# 1602_arduino_ble.net
KiCad netlist of a schematic drawn in EAGLE
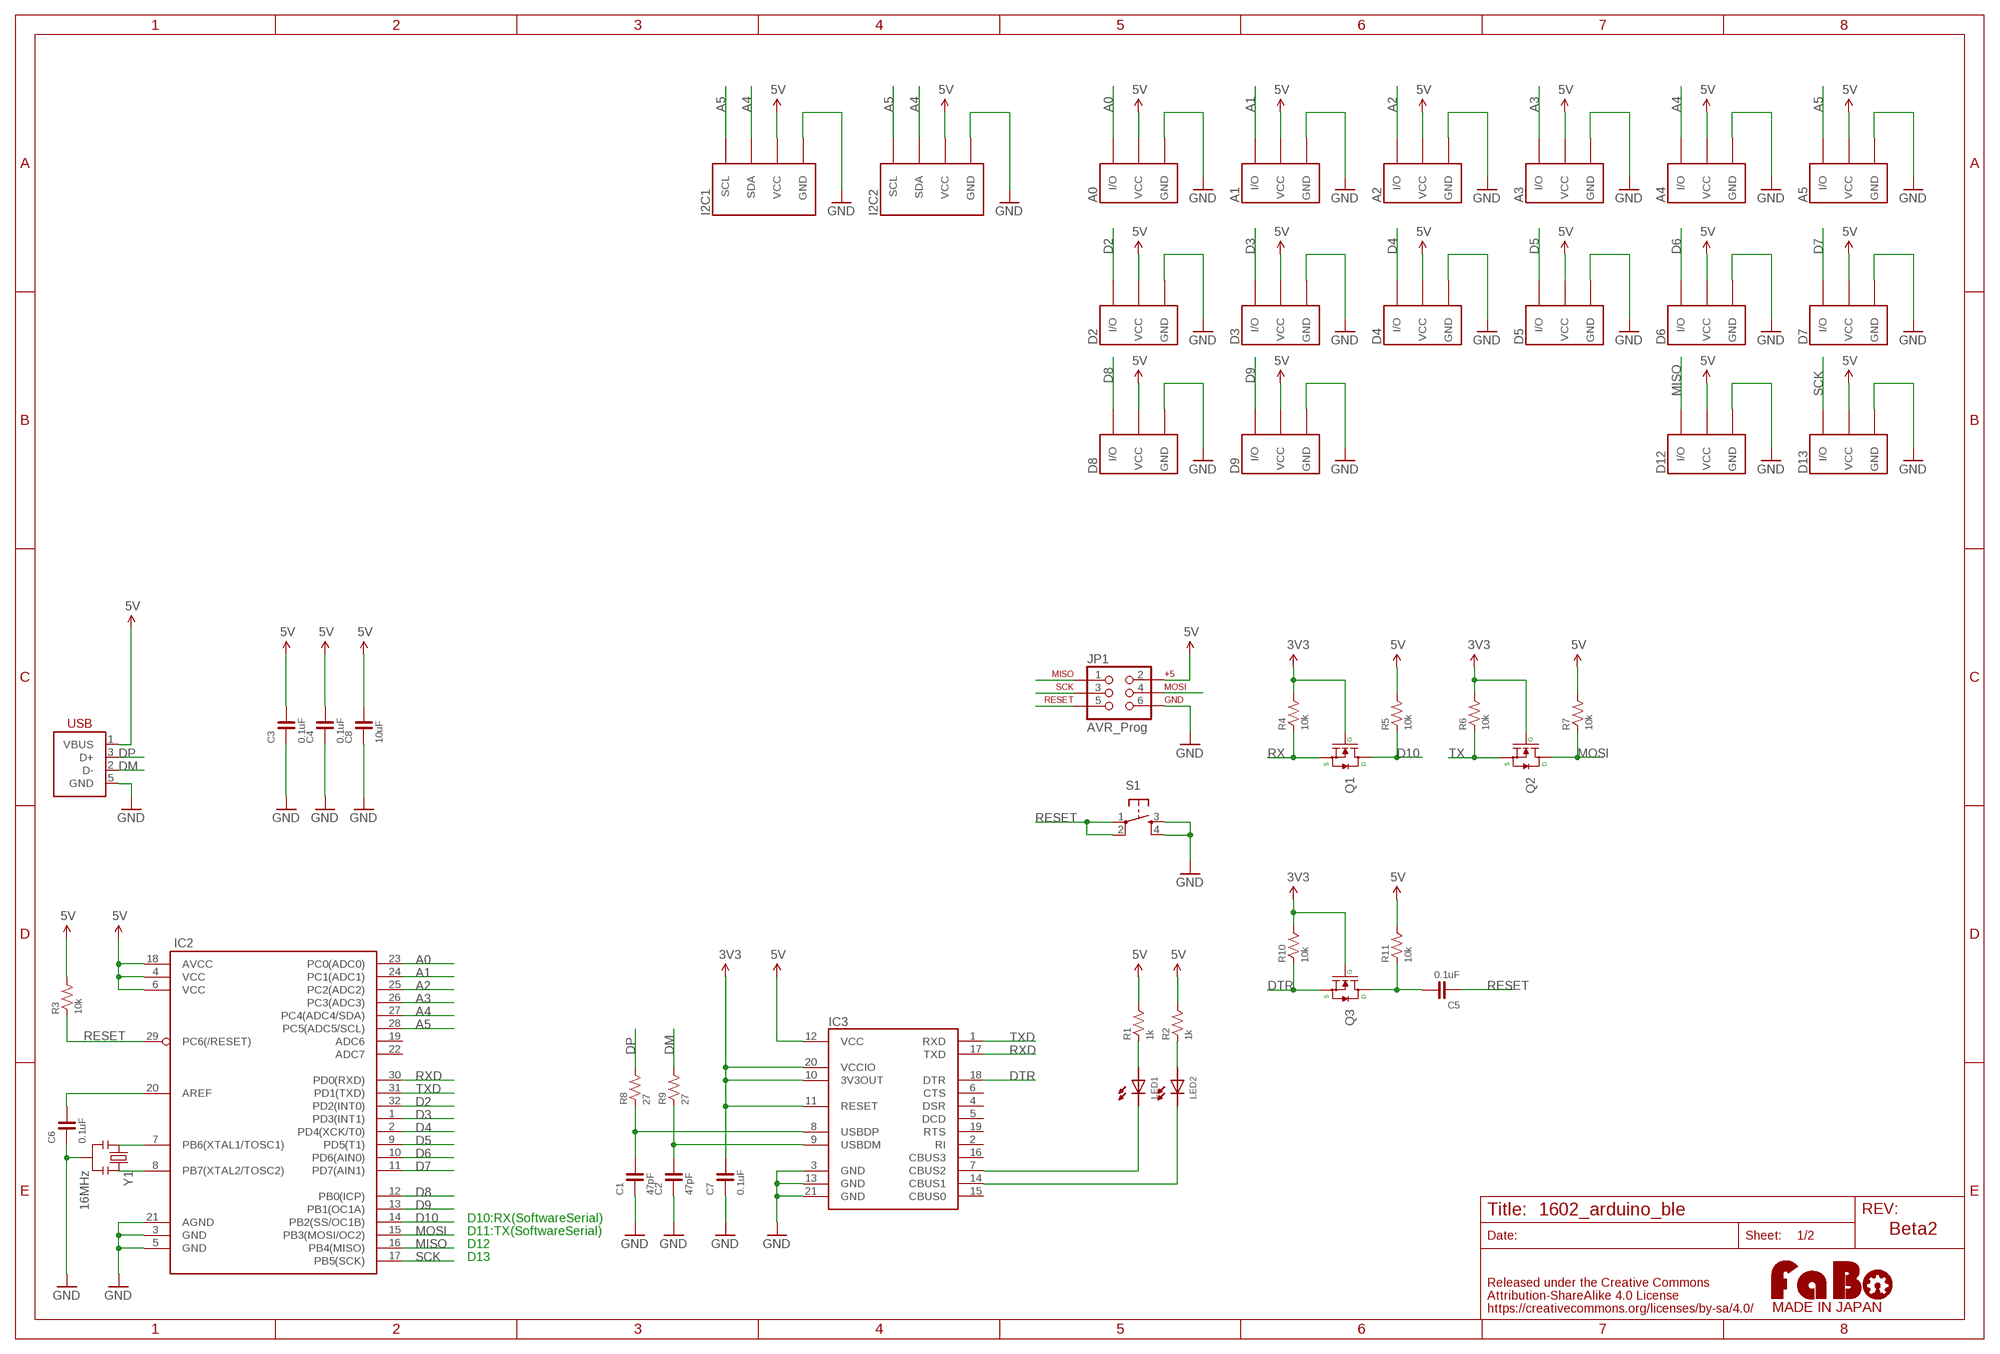
[diagram p0: schematic, sheet 1]
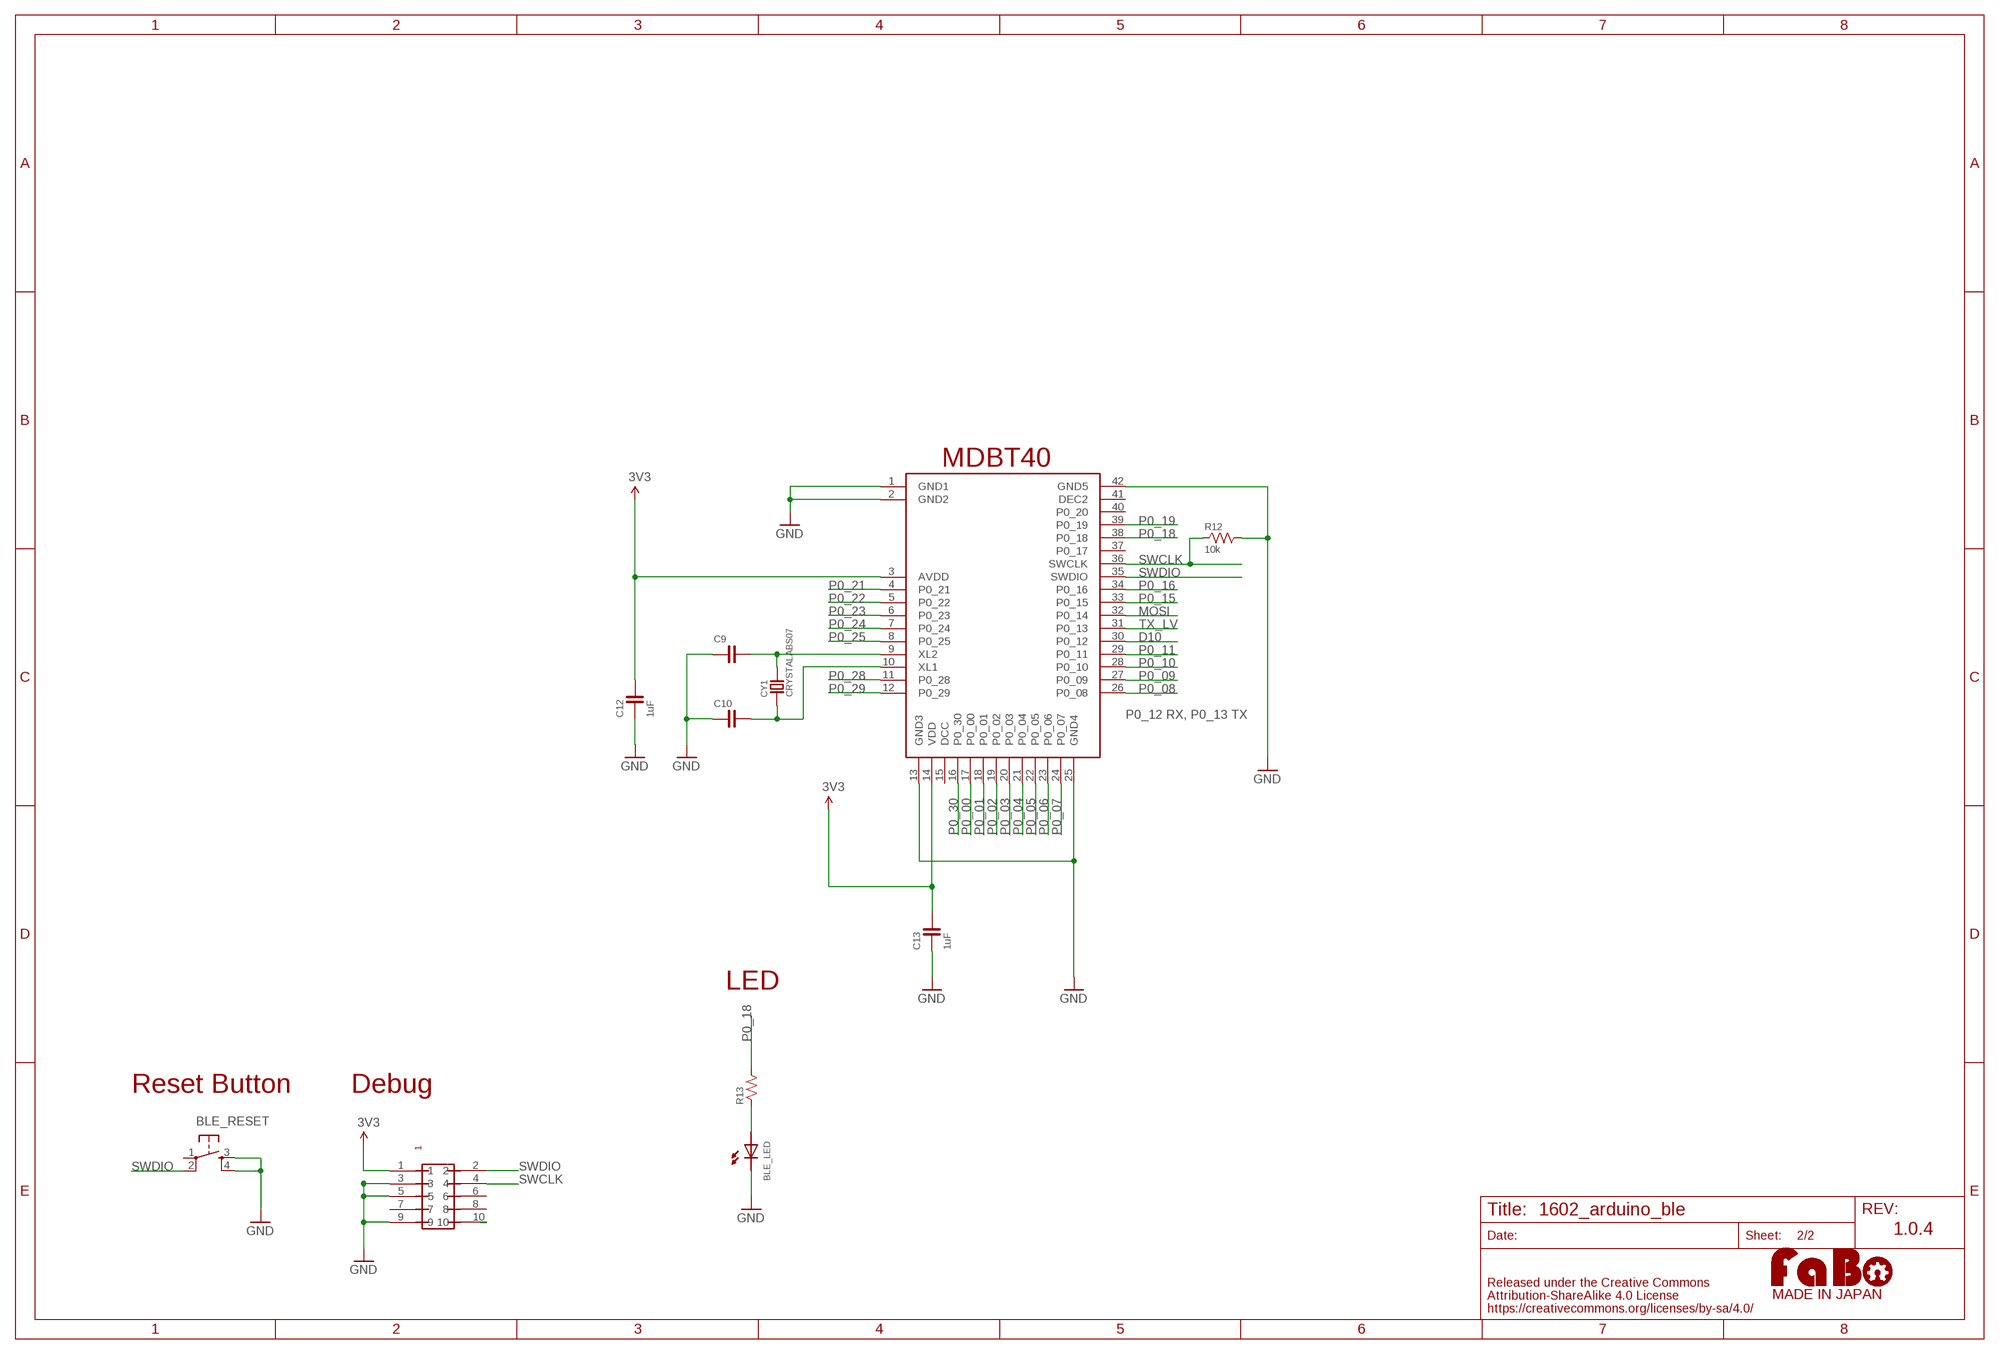
[diagram p1: schematic, sheet 2]

(export (version "E")
  (design (tool "Eeschema 10.0.6"))
  (components
    (comp (ref "A0")
      (value "FABO_BRICK_3PIN-S03B-PASK-2")
      (footprint "eagle-import:FABO_BRICK_3PIN_S03B-PASK-2")
      (libsource (lib "eagle-import") (part "FABO_BRICK_3PIN-S03B-PASK-2"))
    )
    (comp (ref "A1")
      (value "FABO_BRICK_3PIN-S03B-PASK-2")
      (footprint "eagle-import:FABO_BRICK_3PIN_S03B-PASK-2")
      (libsource (lib "eagle-import") (part "FABO_BRICK_3PIN-S03B-PASK-2"))
    )
    (comp (ref "A2")
      (value "FABO_BRICK_3PIN-S03B-PASK-2")
      (footprint "eagle-import:FABO_BRICK_3PIN_S03B-PASK-2")
      (libsource (lib "eagle-import") (part "FABO_BRICK_3PIN-S03B-PASK-2"))
    )
    (comp (ref "A3")
      (value "FABO_BRICK_3PIN-S03B-PASK-2")
      (footprint "eagle-import:FABO_BRICK_3PIN_S03B-PASK-2")
      (libsource (lib "eagle-import") (part "FABO_BRICK_3PIN-S03B-PASK-2"))
    )
    (comp (ref "A4")
      (value "FABO_BRICK_3PIN-S03B-PASK-2")
      (footprint "eagle-import:FABO_BRICK_3PIN_S03B-PASK-2")
      (libsource (lib "eagle-import") (part "FABO_BRICK_3PIN-S03B-PASK-2"))
    )
    (comp (ref "A5")
      (value "FABO_BRICK_3PIN-S03B-PASK-2")
      (footprint "eagle-import:FABO_BRICK_3PIN_S03B-PASK-2")
      (libsource (lib "eagle-import") (part "FABO_BRICK_3PIN-S03B-PASK-2"))
    )
    (comp (ref "C1")
      (value "47pF")
      (footprint "eagle-import:0603")
      (libsource (lib "eagle-import") (part "CAPACITOR-0603"))
    )
    (comp (ref "C2")
      (value "47pF")
      (footprint "eagle-import:0603")
      (libsource (lib "eagle-import") (part "CAPACITOR-0603"))
    )
    (comp (ref "C3")
      (value "0.1uF")
      (footprint "eagle-import:0603")
      (libsource (lib "eagle-import") (part "CAPACITOR-0603"))
    )
    (comp (ref "C4")
      (value "0.1uF")
      (footprint "eagle-import:0603")
      (libsource (lib "eagle-import") (part "CAPACITOR-0603"))
    )
    (comp (ref "C5")
      (value "0.1uF")
      (footprint "eagle-import:0603")
      (libsource (lib "eagle-import") (part "CAPACITOR-0603"))
    )
    (comp (ref "C6")
      (value "0.1uF")
      (footprint "eagle-import:0603")
      (libsource (lib "eagle-import") (part "CAPACITOR-0603"))
    )
    (comp (ref "C7")
      (value "0.1uF")
      (footprint "eagle-import:0603")
      (libsource (lib "eagle-import") (part "CAPACITOR-0603"))
    )
    (comp (ref "C8")
      (value "10uF")
      (footprint "eagle-import:0603")
      (libsource (lib "eagle-import") (part "CAPACITOR-0603"))
    )
    (comp (ref "D2")
      (value "FABO_BRICK_3PIN-B03B-PASK-1")
      (footprint "eagle-import:FABO_BRICK_3PIN_B03B-PASK-1")
      (libsource (lib "eagle-import") (part "FABO_BRICK_3PIN-B03B-PASK-1"))
    )
    (comp (ref "D3")
      (value "FABO_BRICK_3PIN-B03B-PASK-1")
      (footprint "eagle-import:FABO_BRICK_3PIN_B03B-PASK-1")
      (libsource (lib "eagle-import") (part "FABO_BRICK_3PIN-B03B-PASK-1"))
    )
    (comp (ref "D4")
      (value "FABO_BRICK_3PIN-B03B-PASK-1")
      (footprint "eagle-import:FABO_BRICK_3PIN_B03B-PASK-1")
      (libsource (lib "eagle-import") (part "FABO_BRICK_3PIN-B03B-PASK-1"))
    )
    (comp (ref "D5")
      (value "FABO_BRICK_3PIN-B03B-PASK-1")
      (footprint "eagle-import:FABO_BRICK_3PIN_B03B-PASK-1")
      (libsource (lib "eagle-import") (part "FABO_BRICK_3PIN-B03B-PASK-1"))
    )
    (comp (ref "D6")
      (value "FABO_BRICK_3PIN-B03B-PASK-1")
      (footprint "eagle-import:FABO_BRICK_3PIN_B03B-PASK-1")
      (libsource (lib "eagle-import") (part "FABO_BRICK_3PIN-B03B-PASK-1"))
    )
    (comp (ref "D7")
      (value "FABO_BRICK_3PIN-B03B-PASK-1")
      (footprint "eagle-import:FABO_BRICK_3PIN_B03B-PASK-1")
      (libsource (lib "eagle-import") (part "FABO_BRICK_3PIN-B03B-PASK-1"))
    )
    (comp (ref "D8")
      (value "FABO_BRICK_3PIN-B03B-PASK-1")
      (footprint "eagle-import:FABO_BRICK_3PIN_B03B-PASK-1")
      (libsource (lib "eagle-import") (part "FABO_BRICK_3PIN-B03B-PASK-1"))
    )
    (comp (ref "D9")
      (value "FABO_BRICK_3PIN-B03B-PASK-1")
      (footprint "eagle-import:FABO_BRICK_3PIN_B03B-PASK-1")
      (libsource (lib "eagle-import") (part "FABO_BRICK_3PIN-B03B-PASK-1"))
    )
    (comp (ref "D12")
      (value "FABO_BRICK_3PIN-B03B-PASK-1")
      (footprint "eagle-import:FABO_BRICK_3PIN_B03B-PASK-1")
      (libsource (lib "eagle-import") (part "FABO_BRICK_3PIN-B03B-PASK-1"))
    )
    (comp (ref "D13")
      (value "FABO_BRICK_3PIN-B03B-PASK-1")
      (footprint "eagle-import:FABO_BRICK_3PIN_B03B-PASK-1")
      (libsource (lib "eagle-import") (part "FABO_BRICK_3PIN-B03B-PASK-1"))
    )
    (comp (ref "I2C1")
      (value "FABO_BRICK_I2C-S04B-PASK-2")
      (footprint "eagle-import:FABO_BRICK_I2C_S04B-PASK-2")
      (libsource (lib "eagle-import") (part "FABO_BRICK_I2C-S04B-PASK-2"))
    )
    (comp (ref "I2C2")
      (value "FABO_BRICK_I2C-S04B-PASK-2")
      (footprint "eagle-import:FABO_BRICK_I2C_S04B-PASK-2")
      (libsource (lib "eagle-import") (part "FABO_BRICK_I2C-S04B-PASK-2"))
    )
    (comp (ref "IC2")
      (value "ATMEGA328P-AU-TQFP32")
      (footprint "eagle-import:TQFP-32-08")
      (libsource (lib "eagle-import") (part "ATMEGA328P-AU-TQFP32"))
    )
    (comp (ref "IC3")
      (value "FT231XQ")
      (footprint "eagle-import:QFN-20")
      (libsource (lib "eagle-import") (part "FT231XQ"))
    )
    (comp (ref "JP1")
      (value "AVR_Prog")
      (footprint "eagle-import:TC2030-MCP")
      (libsource (lib "eagle-import") (part "AVR_ISP-TC"))
    )
    (comp (ref "LED1")
      (value "LED-0603")
      (footprint "eagle-import:0603")
      (libsource (lib "eagle-import") (part "LED-0603"))
    )
    (comp (ref "LED2")
      (value "LED-0603")
      (footprint "eagle-import:0603")
      (libsource (lib "eagle-import") (part "LED-0603"))
    )
    (comp (ref "Q1")
      (value "MOSFET-N-BSS138")
      (footprint "eagle-import:SOT23-3")
      (libsource (lib "eagle-import") (part "MOSFET-N-BSS138"))
    )
    (comp (ref "Q2")
      (value "MOSFET-N-BSS138")
      (footprint "eagle-import:SOT23-3")
      (libsource (lib "eagle-import") (part "MOSFET-N-BSS138"))
    )
    (comp (ref "Q3")
      (value "MOSFET-N-BSS138")
      (footprint "eagle-import:SOT23-3")
      (libsource (lib "eagle-import") (part "MOSFET-N-BSS138"))
    )
    (comp (ref "R1")
      (value "1k")
      (footprint "eagle-import:0603")
      (libsource (lib "eagle-import") (part "RESISTOR-0603"))
    )
    (comp (ref "R2")
      (value "1k")
      (footprint "eagle-import:0603")
      (libsource (lib "eagle-import") (part "RESISTOR-0603"))
    )
    (comp (ref "R3")
      (value "10k")
      (footprint "eagle-import:0603")
      (libsource (lib "eagle-import") (part "RESISTOR-0603"))
    )
    (comp (ref "R4")
      (value "10k")
      (footprint "eagle-import:0603")
      (libsource (lib "eagle-import") (part "RESISTOR-0603"))
    )
    (comp (ref "R5")
      (value "10k")
      (footprint "eagle-import:0603")
      (libsource (lib "eagle-import") (part "RESISTOR-0603"))
    )
    (comp (ref "R6")
      (value "10k")
      (footprint "eagle-import:0603")
      (libsource (lib "eagle-import") (part "RESISTOR-0603"))
    )
    (comp (ref "R7")
      (value "10k")
      (footprint "eagle-import:0603")
      (libsource (lib "eagle-import") (part "RESISTOR-0603"))
    )
    (comp (ref "R8")
      (value "27")
      (footprint "eagle-import:0603")
      (libsource (lib "eagle-import") (part "RESISTOR-0603"))
    )
    (comp (ref "R9")
      (value "27")
      (footprint "eagle-import:0603")
      (libsource (lib "eagle-import") (part "RESISTOR-0603"))
    )
    (comp (ref "R10")
      (value "10k")
      (footprint "eagle-import:0603")
      (libsource (lib "eagle-import") (part "RESISTOR-0603"))
    )
    (comp (ref "R11")
      (value "10k")
      (footprint "eagle-import:0603")
      (libsource (lib "eagle-import") (part "RESISTOR-0603"))
    )
    (comp (ref "S1")
      (value "TACT-SWITCH-SMD_KMR2")
      (footprint "eagle-import:KMR2")
      (libsource (lib "eagle-import") (part "TACT-SWITCH-SMD_KMR2"))
    )
    (comp (ref "U$3")
      (value "LOGO_FABO-M")
      (footprint "eagle-import:LOGO_FABO_MS")
      (libsource (lib "eagle-import") (part "LOGO_FABO-M"))
    )
    (comp (ref "USB2")
      (value "USB-MICRO_B_SMT")
      (footprint "eagle-import:DX4R005JJ2R1800")
      (libsource (lib "eagle-import") (part "USB-MICRO_B_SMT"))
    )
    (comp (ref "Y1")
      (value "16MHz")
      (footprint "eagle-import:RESONATOR_SMD")
      (libsource (lib "eagle-import") (part "RESONATOR"))
    )
    (comp (ref "BLE_LED")
      (value "LED-0603")
      (footprint "eagle-import:0603")
      (libsource (lib "eagle-import") (part "LED-0603"))
    )
    (comp (ref "BLE_RESET")
      (value "TACT-SWITCH-SMD_KMR2")
      (footprint "eagle-import:KMR2")
      (libsource (lib "eagle-import") (part "TACT-SWITCH-SMD_KMR2"))
    )
    (comp (ref "C9")
      (value "CAPACITOR-0603_NARROW")
      (footprint "eagle-import:0603-NARROW")
      (libsource (lib "eagle-import") (part "CAPACITOR-0603_NARROW"))
    )
    (comp (ref "C10")
      (value "CAPACITOR-0603_NARROW")
      (footprint "eagle-import:0603-NARROW")
      (libsource (lib "eagle-import") (part "CAPACITOR-0603_NARROW"))
    )
    (comp (ref "C12")
      (value "1uF")
      (footprint "eagle-import:0603-NARROW")
      (libsource (lib "eagle-import") (part "CAPACITOR-0603_NARROW"))
    )
    (comp (ref "C13")
      (value "1uF")
      (footprint "eagle-import:0603-NARROW")
      (libsource (lib "eagle-import") (part "CAPACITOR-0603_NARROW"))
    )
    (comp (ref "CY1")
      (value "CRYSTALABS07")
      (footprint "eagle-import:ABRACOM-ABS07-32.768KHZ")
      (libsource (lib "eagle-import") (part "CRYSTALABS07"))
    )
    (comp (ref "R12")
      (value "10k")
      (footprint "eagle-import:0603-NARROW")
      (libsource (lib "eagle-import") (part "RESISTOR-0603-NARROW"))
    )
    (comp (ref "R13")
      (value "RESISTOR-0603-NARROW")
      (footprint "eagle-import:0603-NARROW")
      (libsource (lib "eagle-import") (part "RESISTOR-0603-NARROW"))
    )
    (comp (ref "U$7")
      (value "RAYTAC-MDBT40")
      (footprint "eagle-import:RAYTAC-MDBT40")
      (libsource (lib "eagle-import") (part "RAYTAC-MDBT40"))
    )
    (comp (ref "U$8")
      (value "PIN-HEADER-SMT(1.27MM)2X5")
      (footprint "eagle-import:PIN-HEADER-SMT(1.27MM)2X5")
      (libsource (lib "eagle-import") (part "PIN-HEADER-SMT(1.27MM)2X5"))
    )
    (comp (ref "U$9")
      (value "LOGO_FABO-M_BOTTOM")
      (footprint "eagle-import:LOGO_FABO_MS_BOTTOM")
      (libsource (lib "eagle-import") (part "LOGO_FABO-M_BOTTOM"))
    )
  )
  (nets
    (net (code "1") (name "3V3") (class "Default")
      (node (ref "C12") (pin "2") (pinfunction "2_2") (pintype "passive"))
      (node (ref "C13") (pin "2") (pinfunction "2_2") (pintype "passive"))
      (node (ref "C7") (pin "2") (pinfunction "2_2") (pintype "passive"))
      (node (ref "IC3") (pin "10") (pinfunction "3V3OUT_10") (pintype "bidirectional"))
      (node (ref "IC3") (pin "11") (pinfunction "RESET_11") (pintype "bidirectional"))
      (node (ref "IC3") (pin "20") (pinfunction "VCCIO_20") (pintype "bidirectional"))
      (node (ref "Q1") (pin "1") (pinfunction "G_1") (pintype "passive"))
      (node (ref "Q2") (pin "1") (pinfunction "G_1") (pintype "passive"))
      (node (ref "Q3") (pin "1") (pinfunction "G_1") (pintype "passive"))
      (node (ref "R10") (pin "2") (pinfunction "2_2") (pintype "bidirectional"))
      (node (ref "R4") (pin "2") (pinfunction "2_2") (pintype "bidirectional"))
      (node (ref "R6") (pin "2") (pinfunction "2_2") (pintype "bidirectional"))
      (node (ref "U$7") (pin "14") (pinfunction "VDD_14") (pintype "bidirectional"))
      (node (ref "U$7") (pin "3") (pinfunction "AVDD_3") (pintype "bidirectional"))
      (node (ref "U$8") (pin "1") (pinfunction "1_1") (pintype "bidirectional"))
    )
    (net (code "2") (name "5V") (class "Default")
      (node (ref "A0") (pin "VCC") (pinfunction "VCC_VCC") (pintype "bidirectional"))
      (node (ref "A1") (pin "VCC") (pinfunction "VCC_VCC") (pintype "bidirectional"))
      (node (ref "A2") (pin "VCC") (pinfunction "VCC_VCC") (pintype "bidirectional"))
      (node (ref "A3") (pin "VCC") (pinfunction "VCC_VCC") (pintype "bidirectional"))
      (node (ref "A4") (pin "VCC") (pinfunction "VCC_VCC") (pintype "bidirectional"))
      (node (ref "A5") (pin "VCC") (pinfunction "VCC_VCC") (pintype "bidirectional"))
      (node (ref "C3") (pin "2") (pinfunction "2_2") (pintype "passive"))
      (node (ref "C4") (pin "2") (pinfunction "2_2") (pintype "passive"))
      (node (ref "C8") (pin "2") (pinfunction "2_2") (pintype "passive"))
      (node (ref "D12") (pin "VCC") (pinfunction "VCC_VCC") (pintype "bidirectional"))
      (node (ref "D13") (pin "VCC") (pinfunction "VCC_VCC") (pintype "bidirectional"))
      (node (ref "D2") (pin "VCC") (pinfunction "VCC_VCC") (pintype "bidirectional"))
      (node (ref "D3") (pin "VCC") (pinfunction "VCC_VCC") (pintype "bidirectional"))
      (node (ref "D4") (pin "VCC") (pinfunction "VCC_VCC") (pintype "bidirectional"))
      (node (ref "D5") (pin "VCC") (pinfunction "VCC_VCC") (pintype "bidirectional"))
      (node (ref "D6") (pin "VCC") (pinfunction "VCC_VCC") (pintype "bidirectional"))
      (node (ref "D7") (pin "VCC") (pinfunction "VCC_VCC") (pintype "bidirectional"))
      (node (ref "D8") (pin "VCC") (pinfunction "VCC_VCC") (pintype "bidirectional"))
      (node (ref "D9") (pin "VCC") (pinfunction "VCC_VCC") (pintype "bidirectional"))
      (node (ref "I2C1") (pin "VCC") (pinfunction "VCC_VCC") (pintype "bidirectional"))
      (node (ref "I2C2") (pin "VCC") (pinfunction "VCC_VCC") (pintype "bidirectional"))
      (node (ref "IC2") (pin "18") (pinfunction "AVCC_18") (pintype "bidirectional"))
      (node (ref "IC2") (pin "4") (pinfunction "VCC_4") (pintype "bidirectional"))
      (node (ref "IC2") (pin "6") (pinfunction "VCC_6") (pintype "bidirectional"))
      (node (ref "IC3") (pin "12") (pinfunction "VCC_12") (pintype "bidirectional"))
      (node (ref "JP1") (pin "2") (pinfunction "2_2") (pintype "passive"))
      (node (ref "R1") (pin "2") (pinfunction "2_2") (pintype "bidirectional"))
      (node (ref "R11") (pin "2") (pinfunction "2_2") (pintype "bidirectional"))
      (node (ref "R2") (pin "2") (pinfunction "2_2") (pintype "bidirectional"))
      (node (ref "R3") (pin "2") (pinfunction "2_2") (pintype "bidirectional"))
      (node (ref "R5") (pin "2") (pinfunction "2_2") (pintype "bidirectional"))
      (node (ref "R7") (pin "2") (pinfunction "2_2") (pintype "bidirectional"))
      (node (ref "USB2") (pin "1") (pinfunction "VBUS_1") (pintype "bidirectional"))
    )
    (net (code "3") (name "A0") (class "Default")
      (node (ref "A0") (pin "I/O") (pinfunction "I/O_I/O") (pintype "bidirectional"))
      (node (ref "IC2") (pin "23") (pinfunction "PC0(ADC0)_23") (pintype "bidirectional"))
    )
    (net (code "4") (name "A1") (class "Default")
      (node (ref "A1") (pin "I/O") (pinfunction "I/O_I/O") (pintype "bidirectional"))
      (node (ref "IC2") (pin "24") (pinfunction "PC1(ADC1)_24") (pintype "bidirectional"))
    )
    (net (code "5") (name "A2") (class "Default")
      (node (ref "A2") (pin "I/O") (pinfunction "I/O_I/O") (pintype "bidirectional"))
      (node (ref "IC2") (pin "25") (pinfunction "PC2(ADC2)_25") (pintype "bidirectional"))
    )
    (net (code "6") (name "A3") (class "Default")
      (node (ref "A3") (pin "I/O") (pinfunction "I/O_I/O") (pintype "bidirectional"))
      (node (ref "IC2") (pin "26") (pinfunction "PC3(ADC3)_26") (pintype "bidirectional"))
    )
    (net (code "7") (name "A4") (class "Default")
      (node (ref "A4") (pin "I/O") (pinfunction "I/O_I/O") (pintype "bidirectional"))
      (node (ref "I2C1") (pin "SDA") (pinfunction "SDA_SDA") (pintype "bidirectional"))
      (node (ref "I2C2") (pin "SDA") (pinfunction "SDA_SDA") (pintype "bidirectional"))
      (node (ref "IC2") (pin "27") (pinfunction "PC4(ADC4/SDA)_27") (pintype "bidirectional"))
    )
    (net (code "8") (name "A5") (class "Default")
      (node (ref "A5") (pin "I/O") (pinfunction "I/O_I/O") (pintype "bidirectional"))
      (node (ref "I2C1") (pin "SCL") (pinfunction "SCL_SCL") (pintype "bidirectional"))
      (node (ref "I2C2") (pin "SCL") (pinfunction "SCL_SCL") (pintype "bidirectional"))
      (node (ref "IC2") (pin "28") (pinfunction "PC5(ADC5/SCL)_28") (pintype "bidirectional"))
    )
    (net (code "9") (name "D2") (class "Default")
      (node (ref "D2") (pin "I/O") (pinfunction "I/O_I/O") (pintype "bidirectional"))
      (node (ref "IC2") (pin "32") (pinfunction "PD2(INT0)_32") (pintype "bidirectional"))
    )
    (net (code "10") (name "D3") (class "Default")
      (node (ref "D3") (pin "I/O") (pinfunction "I/O_I/O") (pintype "bidirectional"))
      (node (ref "IC2") (pin "1") (pinfunction "PD3(INT1)_1") (pintype "bidirectional"))
    )
    (net (code "11") (name "D4") (class "Default")
      (node (ref "D4") (pin "I/O") (pinfunction "I/O_I/O") (pintype "bidirectional"))
      (node (ref "IC2") (pin "2") (pinfunction "PD4(XCK/T0)_2") (pintype "bidirectional"))
    )
    (net (code "12") (name "D5") (class "Default")
      (node (ref "D5") (pin "I/O") (pinfunction "I/O_I/O") (pintype "bidirectional"))
      (node (ref "IC2") (pin "9") (pinfunction "PD5(T1)_9") (pintype "bidirectional"))
    )
    (net (code "13") (name "D6") (class "Default")
      (node (ref "D6") (pin "I/O") (pinfunction "I/O_I/O") (pintype "bidirectional"))
      (node (ref "IC2") (pin "10") (pinfunction "PD6(AIN0)_10") (pintype "bidirectional"))
    )
    (net (code "14") (name "D7") (class "Default")
      (node (ref "D7") (pin "I/O") (pinfunction "I/O_I/O") (pintype "bidirectional"))
      (node (ref "IC2") (pin "11") (pinfunction "PD7(AIN1)_11") (pintype "bidirectional"))
    )
    (net (code "15") (name "D8") (class "Default")
      (node (ref "D8") (pin "I/O") (pinfunction "I/O_I/O") (pintype "bidirectional"))
      (node (ref "IC2") (pin "12") (pinfunction "PB0(ICP)_12") (pintype "bidirectional"))
    )
    (net (code "16") (name "D9") (class "Default")
      (node (ref "D9") (pin "I/O") (pinfunction "I/O_I/O") (pintype "bidirectional"))
      (node (ref "IC2") (pin "13") (pinfunction "PB1(OC1A)_13") (pintype "bidirectional"))
    )
    (net (code "17") (name "D10") (class "Default")
      (node (ref "IC2") (pin "14") (pinfunction "PB2(SS/OC1B)_14") (pintype "bidirectional"))
      (node (ref "Q1") (pin "3") (pinfunction "D_3") (pintype "passive"))
      (node (ref "R5") (pin "1") (pinfunction "1_1") (pintype "bidirectional"))
      (node (ref "U$7") (pin "30") (pinfunction "P0_12_30") (pintype "bidirectional"))
    )
    (net (code "18") (name "DM") (class "Default")
      (node (ref "R9") (pin "2") (pinfunction "2_2") (pintype "bidirectional"))
      (node (ref "USB2") (pin "2") (pinfunction "D-_2") (pintype "bidirectional"))
    )
    (net (code "19") (name "DP") (class "Default")
      (node (ref "R8") (pin "2") (pinfunction "2_2") (pintype "bidirectional"))
      (node (ref "USB2") (pin "3") (pinfunction "D+_3") (pintype "bidirectional"))
    )
    (net (code "20") (name "DTR") (class "Default")
      (node (ref "IC3") (pin "18") (pinfunction "DTR_18") (pintype "bidirectional"))
      (node (ref "Q3") (pin "2") (pinfunction "S_2") (pintype "passive"))
      (node (ref "R10") (pin "1") (pinfunction "1_1") (pintype "bidirectional"))
    )
    (net (code "21") (name "GND") (class "Default")
      (node (ref "A0") (pin "GND") (pinfunction "GND_GND") (pintype "bidirectional"))
      (node (ref "A1") (pin "GND") (pinfunction "GND_GND") (pintype "bidirectional"))
      (node (ref "A2") (pin "GND") (pinfunction "GND_GND") (pintype "bidirectional"))
      (node (ref "A3") (pin "GND") (pinfunction "GND_GND") (pintype "bidirectional"))
      (node (ref "A4") (pin "GND") (pinfunction "GND_GND") (pintype "bidirectional"))
      (node (ref "A5") (pin "GND") (pinfunction "GND_GND") (pintype "bidirectional"))
      (node (ref "BLE_LED") (pin "CATHODE") (pinfunction "CATHODE_CATHODE") (pintype "passive"))
      (node (ref "BLE_RESET") (pin "3") (pinfunction "3_3") (pintype "passive"))
      (node (ref "BLE_RESET") (pin "4") (pinfunction "4_4") (pintype "passive"))
      (node (ref "C1") (pin "1") (pinfunction "1_1") (pintype "passive"))
      (node (ref "C10") (pin "1") (pinfunction "1_1") (pintype "passive"))
      (node (ref "C12") (pin "1") (pinfunction "1_1") (pintype "passive"))
      (node (ref "C13") (pin "1") (pinfunction "1_1") (pintype "passive"))
      (node (ref "C2") (pin "1") (pinfunction "1_1") (pintype "passive"))
      (node (ref "C3") (pin "1") (pinfunction "1_1") (pintype "passive"))
      (node (ref "C4") (pin "1") (pinfunction "1_1") (pintype "passive"))
      (node (ref "C6") (pin "1") (pinfunction "1_1") (pintype "passive"))
      (node (ref "C7") (pin "1") (pinfunction "1_1") (pintype "passive"))
      (node (ref "C8") (pin "1") (pinfunction "1_1") (pintype "passive"))
      (node (ref "C9") (pin "1") (pinfunction "1_1") (pintype "passive"))
      (node (ref "D12") (pin "GND") (pinfunction "GND_GND") (pintype "bidirectional"))
      (node (ref "D13") (pin "GND") (pinfunction "GND_GND") (pintype "bidirectional"))
      (node (ref "D2") (pin "GND") (pinfunction "GND_GND") (pintype "bidirectional"))
      (node (ref "D3") (pin "GND") (pinfunction "GND_GND") (pintype "bidirectional"))
      (node (ref "D4") (pin "GND") (pinfunction "GND_GND") (pintype "bidirectional"))
      (node (ref "D5") (pin "GND") (pinfunction "GND_GND") (pintype "bidirectional"))
      (node (ref "D6") (pin "GND") (pinfunction "GND_GND") (pintype "bidirectional"))
      (node (ref "D7") (pin "GND") (pinfunction "GND_GND") (pintype "bidirectional"))
      (node (ref "D8") (pin "GND") (pinfunction "GND_GND") (pintype "bidirectional"))
      (node (ref "D9") (pin "GND") (pinfunction "GND_GND") (pintype "bidirectional"))
      (node (ref "I2C1") (pin "GND") (pinfunction "GND_GND") (pintype "bidirectional"))
      (node (ref "I2C2") (pin "GND") (pinfunction "GND_GND") (pintype "bidirectional"))
      (node (ref "IC2") (pin "21") (pinfunction "AGND_21") (pintype "bidirectional"))
      (node (ref "IC2") (pin "3") (pinfunction "GND_3") (pintype "bidirectional"))
      (node (ref "IC2") (pin "5") (pinfunction "GND_5") (pintype "bidirectional"))
      (node (ref "IC3") (pin "13") (pinfunction "GND_13") (pintype "bidirectional"))
      (node (ref "IC3") (pin "21") (pinfunction "GND_21") (pintype "bidirectional"))
      (node (ref "IC3") (pin "3") (pinfunction "GND_3") (pintype "bidirectional"))
      (node (ref "JP1") (pin "6") (pinfunction "6_6") (pintype "passive"))
      (node (ref "R12") (pin "2") (pinfunction "2_2") (pintype "bidirectional"))
      (node (ref "S1") (pin "3") (pinfunction "3_3") (pintype "passive"))
      (node (ref "S1") (pin "4") (pinfunction "4_4") (pintype "passive"))
      (node (ref "U$7") (pin "1") (pinfunction "GND1_1") (pintype "bidirectional"))
      (node (ref "U$7") (pin "13") (pinfunction "GND3_13") (pintype "bidirectional"))
      (node (ref "U$7") (pin "2") (pinfunction "GND2_2") (pintype "bidirectional"))
      (node (ref "U$7") (pin "25") (pinfunction "GND4_25") (pintype "bidirectional"))
      (node (ref "U$7") (pin "42") (pinfunction "GND5_42") (pintype "bidirectional"))
      (node (ref "U$8") (pin "3") (pinfunction "3_3") (pintype "bidirectional"))
      (node (ref "U$8") (pin "5") (pinfunction "5_5") (pintype "bidirectional"))
      (node (ref "U$8") (pin "9") (pinfunction "9_9") (pintype "bidirectional"))
      (node (ref "USB2") (pin "5") (pinfunction "GND_5") (pintype "bidirectional"))
      (node (ref "Y1") (pin "2") (pinfunction "2_2") (pintype "passive"))
    )
    (net (code "22") (name "MISO") (class "Default")
      (node (ref "D12") (pin "I/O") (pinfunction "I/O_I/O") (pintype "bidirectional"))
      (node (ref "IC2") (pin "16") (pinfunction "PB4(MISO)_16") (pintype "bidirectional"))
      (node (ref "JP1") (pin "1") (pinfunction "1_1") (pintype "passive"))
    )
    (net (code "23") (name "MOSI") (class "Default")
      (node (ref "IC2") (pin "15") (pinfunction "PB3(MOSI/OC2)_15") (pintype "bidirectional"))
      (node (ref "JP1") (pin "4") (pinfunction "4_4") (pintype "passive"))
      (node (ref "Q2") (pin "3") (pinfunction "D_3") (pintype "passive"))
      (node (ref "R7") (pin "1") (pinfunction "1_1") (pintype "bidirectional"))
      (node (ref "U$7") (pin "32") (pinfunction "P0_14_32") (pintype "bidirectional"))
    )
    (net (code "24") (name "Net-(BLE_LED-PadANODE)") (class "Default")
      (node (ref "BLE_LED") (pin "ANODE") (pinfunction "ANODE_ANODE") (pintype "passive"))
      (node (ref "R13") (pin "1") (pinfunction "1_1") (pintype "bidirectional"))
    )
    (net (code "25") (name "Net-(IC2-AREF)") (class "Default")
      (node (ref "C6") (pin "2") (pinfunction "2_2") (pintype "passive"))
      (node (ref "IC2") (pin "20") (pinfunction "AREF_20") (pintype "bidirectional"))
    )
    (net (code "26") (name "Net-(IC2-PB6(XTAL1{slash}TOSC1))") (class "Default")
      (node (ref "IC2") (pin "7") (pinfunction "PB6(XTAL1/TOSC1)_7") (pintype "bidirectional"))
      (node (ref "Y1") (pin "1") (pinfunction "1_1") (pintype "passive"))
    )
    (net (code "27") (name "Net-(IC2-PB7(XTAL2{slash}TOSC2))") (class "Default")
      (node (ref "IC2") (pin "8") (pinfunction "PB7(XTAL2/TOSC2)_8") (pintype "bidirectional"))
      (node (ref "Y1") (pin "3") (pinfunction "3_3") (pintype "passive"))
    )
    (net (code "28") (name "Net-(IC3-CBUS1)") (class "Default")
      (node (ref "IC3") (pin "14") (pinfunction "CBUS1_14") (pintype "bidirectional"))
      (node (ref "LED2") (pin "CATHODE") (pinfunction "CATHODE_CATHODE") (pintype "passive"))
    )
    (net (code "29") (name "Net-(IC3-CBUS2)") (class "Default")
      (node (ref "IC3") (pin "7") (pinfunction "CBUS2_7") (pintype "bidirectional"))
      (node (ref "LED1") (pin "CATHODE") (pinfunction "CATHODE_CATHODE") (pintype "passive"))
    )
    (net (code "30") (name "Net-(IC3-USBDM)") (class "Default")
      (node (ref "C2") (pin "2") (pinfunction "2_2") (pintype "passive"))
      (node (ref "IC3") (pin "9") (pinfunction "USBDM_9") (pintype "bidirectional"))
      (node (ref "R9") (pin "1") (pinfunction "1_1") (pintype "bidirectional"))
    )
    (net (code "31") (name "Net-(IC3-USBDP)") (class "Default")
      (node (ref "C1") (pin "2") (pinfunction "2_2") (pintype "passive"))
      (node (ref "IC3") (pin "8") (pinfunction "USBDP_8") (pintype "bidirectional"))
      (node (ref "R8") (pin "1") (pinfunction "1_1") (pintype "bidirectional"))
    )
    (net (code "32") (name "Net-(LED1-PadANODE)") (class "Default")
      (node (ref "LED1") (pin "ANODE") (pinfunction "ANODE_ANODE") (pintype "passive"))
      (node (ref "R1") (pin "1") (pinfunction "1_1") (pintype "bidirectional"))
    )
    (net (code "33") (name "Net-(LED2-PadANODE)") (class "Default")
      (node (ref "LED2") (pin "ANODE") (pinfunction "ANODE_ANODE") (pintype "passive"))
      (node (ref "R2") (pin "1") (pinfunction "1_1") (pintype "bidirectional"))
    )
    (net (code "34") (name "Net-(Q3-D)") (class "Default")
      (node (ref "C5") (pin "2") (pinfunction "2_2") (pintype "passive"))
      (node (ref "Q3") (pin "3") (pinfunction "D_3") (pintype "passive"))
      (node (ref "R11") (pin "1") (pinfunction "1_1") (pintype "bidirectional"))
    )
    (net (code "35") (name "Net-(U$7-XL1)") (class "Default")
      (node (ref "C10") (pin "2") (pinfunction "2_2") (pintype "passive"))
      (node (ref "CY1") (pin "P$1") (pinfunction "P$1_P$1") (pintype "bidirectional"))
      (node (ref "U$7") (pin "10") (pinfunction "XL1_10") (pintype "bidirectional"))
    )
    (net (code "36") (name "Net-(U$7-XL2)") (class "Default")
      (node (ref "C9") (pin "2") (pinfunction "2_2") (pintype "passive"))
      (node (ref "CY1") (pin "P$2") (pinfunction "P$2_P$2") (pintype "bidirectional"))
      (node (ref "U$7") (pin "9") (pinfunction "XL2_9") (pintype "bidirectional"))
    )
    (net (code "37") (name "P0_00") (class "Default")
      (node (ref "U$7") (pin "17") (pinfunction "P0_00_17") (pintype "bidirectional"))
    )
    (net (code "38") (name "P0_01") (class "Default")
      (node (ref "U$7") (pin "18") (pinfunction "P0_01_18") (pintype "bidirectional"))
    )
    (net (code "39") (name "P0_02") (class "Default")
      (node (ref "U$7") (pin "19") (pinfunction "P0_02_19") (pintype "bidirectional"))
    )
    (net (code "40") (name "P0_03") (class "Default")
      (node (ref "U$7") (pin "20") (pinfunction "P0_03_20") (pintype "bidirectional"))
    )
    (net (code "41") (name "P0_04") (class "Default")
      (node (ref "U$7") (pin "21") (pinfunction "P0_04_21") (pintype "bidirectional"))
    )
    (net (code "42") (name "P0_05") (class "Default")
      (node (ref "U$7") (pin "22") (pinfunction "P0_05_22") (pintype "bidirectional"))
    )
    (net (code "43") (name "P0_06") (class "Default")
      (node (ref "U$7") (pin "23") (pinfunction "P0_06_23") (pintype "bidirectional"))
    )
    (net (code "44") (name "P0_07") (class "Default")
      (node (ref "U$7") (pin "24") (pinfunction "P0_07_24") (pintype "bidirectional"))
    )
    (net (code "45") (name "P0_08") (class "Default")
      (node (ref "U$7") (pin "26") (pinfunction "P0_08_26") (pintype "bidirectional"))
    )
    (net (code "46") (name "P0_09") (class "Default")
      (node (ref "U$7") (pin "27") (pinfunction "P0_09_27") (pintype "bidirectional"))
    )
    (net (code "47") (name "P0_10") (class "Default")
      (node (ref "U$7") (pin "28") (pinfunction "P0_10_28") (pintype "bidirectional"))
    )
    (net (code "48") (name "P0_11") (class "Default")
      (node (ref "U$7") (pin "29") (pinfunction "P0_11_29") (pintype "bidirectional"))
    )
    (net (code "49") (name "P0_15") (class "Default")
      (node (ref "U$7") (pin "33") (pinfunction "P0_15_33") (pintype "bidirectional"))
    )
    (net (code "50") (name "P0_16") (class "Default")
      (node (ref "U$7") (pin "34") (pinfunction "P0_16_34") (pintype "bidirectional"))
    )
    (net (code "51") (name "P0_18") (class "Default")
      (node (ref "R13") (pin "2") (pinfunction "2_2") (pintype "bidirectional"))
      (node (ref "U$7") (pin "38") (pinfunction "P0_18_38") (pintype "bidirectional"))
    )
    (net (code "52") (name "P0_19") (class "Default")
      (node (ref "U$7") (pin "39") (pinfunction "P0_19_39") (pintype "bidirectional"))
    )
    (net (code "53") (name "P0_21") (class "Default")
      (node (ref "U$7") (pin "4") (pinfunction "P0_21_4") (pintype "bidirectional"))
    )
    (net (code "54") (name "P0_22") (class "Default")
      (node (ref "U$7") (pin "5") (pinfunction "P0_22_5") (pintype "bidirectional"))
    )
    (net (code "55") (name "P0_23") (class "Default")
      (node (ref "U$7") (pin "6") (pinfunction "P0_23_6") (pintype "bidirectional"))
    )
    (net (code "56") (name "P0_24") (class "Default")
      (node (ref "U$7") (pin "7") (pinfunction "P0_24_7") (pintype "bidirectional"))
    )
    (net (code "57") (name "P0_25") (class "Default")
      (node (ref "U$7") (pin "8") (pinfunction "P0_25_8") (pintype "bidirectional"))
    )
    (net (code "58") (name "P0_28") (class "Default")
      (node (ref "U$7") (pin "11") (pinfunction "P0_28_11") (pintype "bidirectional"))
    )
    (net (code "59") (name "P0_29") (class "Default")
      (node (ref "U$7") (pin "12") (pinfunction "P0_29_12") (pintype "bidirectional"))
    )
    (net (code "60") (name "P0_30") (class "Default")
      (node (ref "U$7") (pin "16") (pinfunction "P0_30_16") (pintype "bidirectional"))
    )
    (net (code "61") (name "RESET") (class "Default")
      (node (ref "C5") (pin "1") (pinfunction "1_1") (pintype "passive"))
      (node (ref "IC2") (pin "29") (pinfunction "PC6(/RESET)_29") (pintype "bidirectional"))
      (node (ref "JP1") (pin "5") (pinfunction "5_5") (pintype "passive"))
      (node (ref "R3") (pin "1") (pinfunction "1_1") (pintype "bidirectional"))
      (node (ref "S1") (pin "1") (pinfunction "1_1") (pintype "passive"))
      (node (ref "S1") (pin "2") (pinfunction "2_2") (pintype "passive"))
    )
    (net (code "62") (name "RX") (class "Default")
      (node (ref "Q1") (pin "2") (pinfunction "S_2") (pintype "passive"))
      (node (ref "R4") (pin "1") (pinfunction "1_1") (pintype "bidirectional"))
    )
    (net (code "63") (name "RXD") (class "Default")
      (node (ref "IC2") (pin "30") (pinfunction "PD0(RXD)_30") (pintype "bidirectional"))
      (node (ref "IC3") (pin "17") (pinfunction "TXD_17") (pintype "bidirectional"))
    )
    (net (code "64") (name "SCK") (class "Default")
      (node (ref "D13") (pin "I/O") (pinfunction "I/O_I/O") (pintype "bidirectional"))
      (node (ref "IC2") (pin "17") (pinfunction "PB5(SCK)_17") (pintype "bidirectional"))
      (node (ref "JP1") (pin "3") (pinfunction "3_3") (pintype "passive"))
    )
    (net (code "65") (name "SWCLK") (class "Default")
      (node (ref "R12") (pin "1") (pinfunction "1_1") (pintype "bidirectional"))
      (node (ref "U$7") (pin "36") (pinfunction "SWCLK_36") (pintype "bidirectional"))
      (node (ref "U$8") (pin "4") (pinfunction "4_4") (pintype "bidirectional"))
    )
    (net (code "66") (name "SWDIO") (class "Default")
      (node (ref "BLE_RESET") (pin "2") (pinfunction "2_2") (pintype "passive"))
      (node (ref "U$7") (pin "35") (pinfunction "SWDIO_35") (pintype "bidirectional"))
      (node (ref "U$8") (pin "2") (pinfunction "2_2") (pintype "bidirectional"))
    )
    (net (code "67") (name "TX") (class "Default")
      (node (ref "Q2") (pin "2") (pinfunction "S_2") (pintype "passive"))
      (node (ref "R6") (pin "1") (pinfunction "1_1") (pintype "bidirectional"))
    )
    (net (code "68") (name "TXD") (class "Default")
      (node (ref "IC2") (pin "31") (pinfunction "PD1(TXD)_31") (pintype "bidirectional"))
      (node (ref "IC3") (pin "1") (pinfunction "RXD_1") (pintype "bidirectional"))
    )
    (net (code "69") (name "TX_LV") (class "Default")
      (node (ref "U$7") (pin "31") (pinfunction "P0_13_31") (pintype "bidirectional"))
    )
    (net (code "70") (name "unconnected-(BLE_RESET-Pad1)") (class "Default")
      (node (ref "BLE_RESET") (pin "1") (pinfunction "1_1") (pintype "passive"))
    )
    (net (code "71") (name "unconnected-(IC2-ADC6-Pad19)") (class "Default")
      (node (ref "IC2") (pin "19") (pinfunction "ADC6_19") (pintype "bidirectional"))
    )
    (net (code "72") (name "unconnected-(IC2-ADC7-Pad22)") (class "Default")
      (node (ref "IC2") (pin "22") (pinfunction "ADC7_22") (pintype "bidirectional"))
    )
    (net (code "73") (name "unconnected-(IC3-CBUS0-Pad15)") (class "Default")
      (node (ref "IC3") (pin "15") (pinfunction "CBUS0_15") (pintype "bidirectional"))
    )
    (net (code "74") (name "unconnected-(IC3-CBUS3-Pad16)") (class "Default")
      (node (ref "IC3") (pin "16") (pinfunction "CBUS3_16") (pintype "bidirectional"))
    )
    (net (code "75") (name "unconnected-(IC3-CTS-Pad6)") (class "Default")
      (node (ref "IC3") (pin "6") (pinfunction "CTS_6") (pintype "bidirectional"))
    )
    (net (code "76") (name "unconnected-(IC3-DCD-Pad5)") (class "Default")
      (node (ref "IC3") (pin "5") (pinfunction "DCD_5") (pintype "bidirectional"))
    )
    (net (code "77") (name "unconnected-(IC3-DSR-Pad4)") (class "Default")
      (node (ref "IC3") (pin "4") (pinfunction "DSR_4") (pintype "bidirectional"))
    )
    (net (code "78") (name "unconnected-(IC3-RI-Pad2)") (class "Default")
      (node (ref "IC3") (pin "2") (pinfunction "RI_2") (pintype "bidirectional"))
    )
    (net (code "79") (name "unconnected-(IC3-RTS-Pad19)") (class "Default")
      (node (ref "IC3") (pin "19") (pinfunction "RTS_19") (pintype "bidirectional"))
    )
    (net (code "80") (name "unconnected-(U$7-DCC-Pad15)") (class "Default")
      (node (ref "U$7") (pin "15") (pinfunction "DCC_15") (pintype "bidirectional"))
    )
    (net (code "81") (name "unconnected-(U$7-DEC2-Pad41)") (class "Default")
      (node (ref "U$7") (pin "41") (pinfunction "DEC2_41") (pintype "bidirectional"))
    )
    (net (code "82") (name "unconnected-(U$7-P0_17-Pad37)") (class "Default")
      (node (ref "U$7") (pin "37") (pinfunction "P0_17_37") (pintype "bidirectional"))
    )
    (net (code "83") (name "unconnected-(U$7-P0_20-Pad40)") (class "Default")
      (node (ref "U$7") (pin "40") (pinfunction "P0_20_40") (pintype "bidirectional"))
    )
    (net (code "84") (name "unconnected-(U$8-Pad6)") (class "Default")
      (node (ref "U$8") (pin "6") (pinfunction "6_6") (pintype "bidirectional"))
    )
    (net (code "85") (name "unconnected-(U$8-Pad7)") (class "Default")
      (node (ref "U$8") (pin "7") (pinfunction "7_7") (pintype "bidirectional"))
    )
    (net (code "86") (name "unconnected-(U$8-Pad8)") (class "Default")
      (node (ref "U$8") (pin "8") (pinfunction "8_8") (pintype "bidirectional"))
    )
    (net (code "87") (name "unconnected-(U$8-Pad10)") (class "Default")
      (node (ref "U$8") (pin "10") (pinfunction "10_10") (pintype "bidirectional"))
    )
  )
)
